# PlugEVSE_1x32A.net
KiCad netlist of a schematic drawn in EAGLE
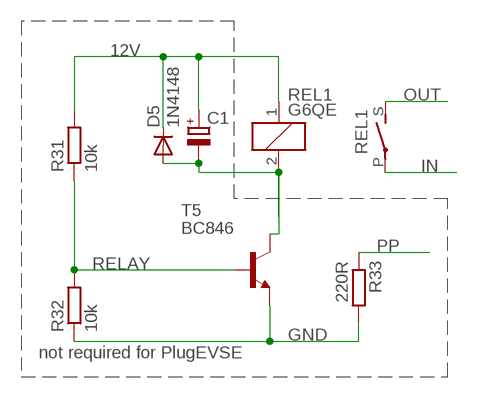
[diagram p0: schematic, sheet 1]

(export (version "E")
  (design (tool "Eeschema 10.0.6"))
  (components
    (comp (ref "C1")
      (value "CPOL-EUSMCC")
      (footprint "eagle-import:SMC_C")
      (libsource (lib "eagle-import") (part "CPOL-EUSMCC"))
    )
    (comp (ref "D5")
      (value "1N4148")
      (footprint "eagle-import:SOD123")
      (libsource (lib "eagle-import") (part "DIODE-SOD123"))
    )
    (comp (ref "R31")
      (value "10k")
      (footprint "eagle-import:R0603")
      (libsource (lib "eagle-import") (part "rcl_334_R-EU_R0603"))
    )
    (comp (ref "R32")
      (value "10k")
      (footprint "eagle-import:R0603")
      (libsource (lib "eagle-import") (part "rcl_334_R-EU_R0603"))
    )
    (comp (ref "R33")
      (value "220R")
      (footprint "eagle-import:R2512")
      (libsource (lib "eagle-import") (part "R-EU_R2512"))
    )
    (comp (ref "REL1")
      (value "G6QE")
      (footprint "eagle-import:G6QE")
      (libsource (lib "eagle-import") (part "G6QE"))
    )
    (comp (ref "T5")
      (value "BC846")
      (footprint "eagle-import:SOT23")
      (libsource (lib "eagle-import") (part "BC846"))
    )
  )
  (nets
    (net (code "1") (name "/12V") (class "Default")
      (node (ref "C1") (pin "+") (pinfunction "+_+") (pintype "passive"))
      (node (ref "D5") (pin "C") (pinfunction "C_C") (pintype "passive"))
      (node (ref "R31") (pin "2") (pinfunction "2_2") (pintype "passive"))
      (node (ref "REL1") (pin "1") (pinfunction "1_1") (pintype "passive"))
    )
    (net (code "2") (name "/GND") (class "Default")
      (node (ref "R32") (pin "1") (pinfunction "1_1") (pintype "passive"))
      (node (ref "R33") (pin "2") (pinfunction "2_2") (pintype "passive"))
      (node (ref "T5") (pin "2") (pinfunction "E_2") (pintype "passive"))
    )
    (net (code "3") (name "/IN") (class "Default")
      (node (ref "REL1") (pin "P") (pinfunction "P_P") (pintype "passive"))
    )
    (net (code "4") (name "/OUT") (class "Default")
      (node (ref "REL1") (pin "S") (pinfunction "S_S") (pintype "passive"))
    )
    (net (code "5") (name "/PP") (class "Default")
      (node (ref "R33") (pin "1") (pinfunction "1_1") (pintype "passive"))
    )
    (net (code "6") (name "/RELAY") (class "Default")
      (node (ref "R31") (pin "1") (pinfunction "1_1") (pintype "passive"))
      (node (ref "R32") (pin "2") (pinfunction "2_2") (pintype "passive"))
      (node (ref "T5") (pin "1") (pinfunction "B_1") (pintype "passive"))
    )
    (net (code "7") (name "Net-(T5-C)") (class "Default")
      (node (ref "C1") (pin "-") (pinfunction "-_-") (pintype "passive"))
      (node (ref "D5") (pin "A") (pinfunction "A_A") (pintype "passive"))
      (node (ref "REL1") (pin "2") (pinfunction "2_2") (pintype "passive"))
      (node (ref "T5") (pin "3") (pinfunction "C_3") (pintype "passive"))
    )
  )
)
